# Copy_of_Sheet1.net
KiCad netlist of a schematic drawn in Altium Designer
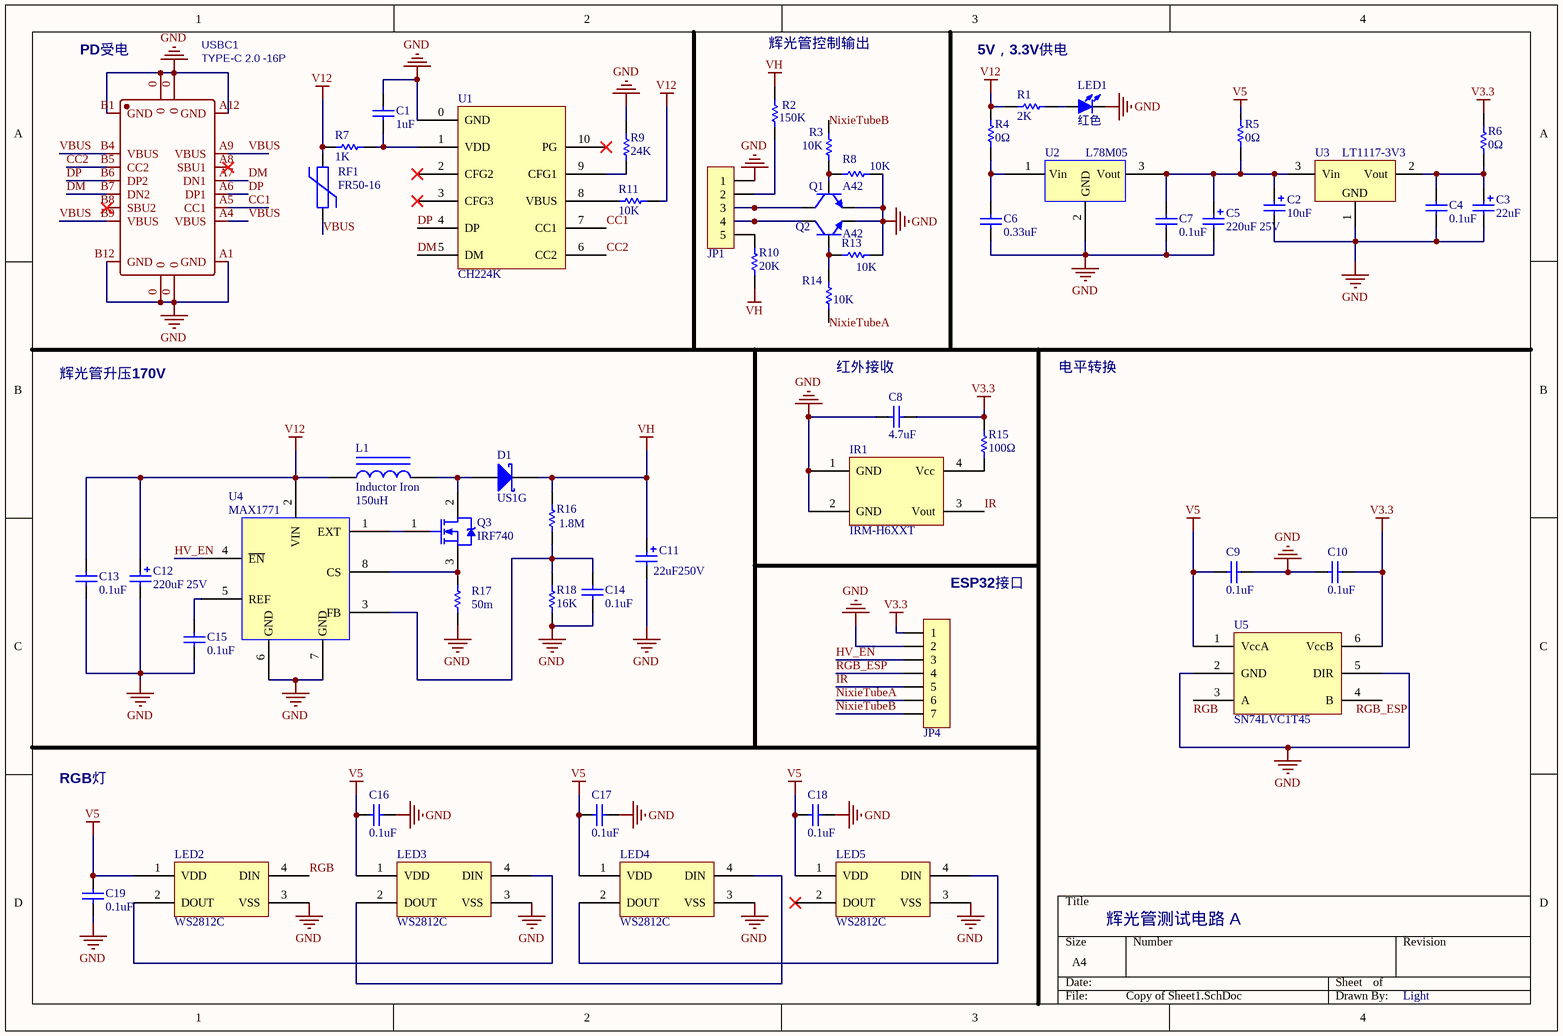
[diagram p0: Copy of Sheet1.SchDoc]

(export (version "E")
  (design (tool "Eeschema 10.0.6"))
  (components
    (comp (ref "C1")
      (value "1uF")
      (footprint "C 0805_L")
      (description "Capacitor")
      (fields (field (name "Comment") "Cap") (field (name "PUBLISHER") "Altium Limited"))
      (libsource (lib "Nixie") (part "Cap"))
    )
    (comp (ref "C2")
      (value "10uF")
      (footprint "CM B(4*5.4)")
      (description "Polarized Capacitor (Radial)")
      (fields (field (name "Comment") "Cap Pol1") (field (name "PUBLISHER") "Altium Limited"))
      (libsource (lib "Nixie") (part "Cap Pol1"))
    )
    (comp (ref "C3")
      (value "22uF")
      (footprint "CD C(6032)")
      (description "Polarized Capacitor (Radial)")
      (fields (field (name "Comment") "Cap Pol1") (field (name "PUBLISHER") "Altium Limited"))
      (libsource (lib "Nixie") (part "Cap Pol1"))
    )
    (comp (ref "C4")
      (value "0.1uF")
      (footprint "C 0805_L")
      (description "Capacitor")
      (fields (field (name "Comment") "Cap") (field (name "PUBLISHER") "Altium Limited"))
      (libsource (lib "Nixie") (part "Cap"))
    )
    (comp (ref "C5")
      (value "220uF 25V")
      (footprint "CM E(8*10.2)")
      (description "Polarized Capacitor (Radial)")
      (fields
        (field (name "VOLTAGE") "16V")
        (field (name "Comment") "Cap Pol1")
        (field (name "PUBLISHER") "Altium Limited")
      )
      (libsource (lib "Nixie") (part "Cap Pol1_2"))
    )
    (comp (ref "C6")
      (value "0.33uF")
      (footprint "C 0805_L")
      (description "Capacitor")
      (fields (field (name "Comment") "Cap") (field (name "PUBLISHER") "Altium Limited"))
      (libsource (lib "Nixie") (part "Cap"))
    )
    (comp (ref "C7")
      (value "0.1uF")
      (footprint "C 0805_L")
      (description "Capacitor")
      (fields (field (name "Comment") "Cap") (field (name "PUBLISHER") "Altium Limited"))
      (libsource (lib "Nixie") (part "Cap"))
    )
    (comp (ref "C8")
      (value "4.7uF")
      (footprint "C 0805_L")
      (description "Capacitor")
      (fields (field (name "Comment") "Cap") (field (name "PUBLISHER") "Altium Limited"))
      (libsource (lib "Nixie") (part "Cap"))
    )
    (comp (ref "C9")
      (value "0.1uF")
      (footprint "C 0805_L")
      (description "Capacitor")
      (fields (field (name "Comment") "Cap") (field (name "PUBLISHER") "Altium Limited"))
      (libsource (lib "Nixie") (part "Cap"))
    )
    (comp (ref "C10")
      (value "0.1uF")
      (footprint "C 0805_L")
      (description "Capacitor")
      (fields (field (name "Comment") "Cap") (field (name "PUBLISHER") "Altium Limited"))
      (libsource (lib "Nixie") (part "Cap"))
    )
    (comp (ref "C11")
      (value "22uF250V")
      (footprint "CAP 5.0*10*16-H - GD")
      (description "Polarized Capacitor (Radial)")
      (fields (field (name "Comment") "Cap Pol1") (field (name "PUBLISHER") "Altium Limited"))
      (libsource (lib "Nixie") (part "Cap Pol1_3"))
    )
    (comp (ref "C12")
      (value "220uF 25V")
      (footprint "CM E(8*10.2)")
      (description "Polarized Capacitor (Radial)")
      (fields
        (field (name "VOLTAGE") "16V")
        (field (name "Comment") "Cap Pol1")
        (field (name "PUBLISHER") "Altium Limited")
      )
      (libsource (lib "Nixie") (part "Cap Pol1_2"))
    )
    (comp (ref "C13")
      (value "0.1uF")
      (footprint "C 0805_L")
      (description "Capacitor")
      (fields (field (name "Comment") "Cap") (field (name "PUBLISHER") "Altium Limited"))
      (libsource (lib "Nixie") (part "Cap"))
    )
    (comp (ref "C14")
      (value "0.1uF")
      (footprint "C 0805_L")
      (description "Capacitor")
      (fields (field (name "Comment") "Cap") (field (name "PUBLISHER") "Altium Limited"))
      (libsource (lib "Nixie") (part "Cap"))
    )
    (comp (ref "C15")
      (value "0.1uF")
      (footprint "C 0805_L")
      (description "Capacitor")
      (fields (field (name "Comment") "Cap") (field (name "PUBLISHER") "Altium Limited"))
      (libsource (lib "Schlib1") (part "Cap"))
    )
    (comp (ref "C16")
      (value "0.1uF")
      (footprint "C 0805_L")
      (description "Capacitor")
      (fields (field (name "Comment") "Cap") (field (name "PUBLISHER") "Altium Limited"))
      (libsource (lib "Nixie") (part "Cap"))
    )
    (comp (ref "C17")
      (value "0.1uF")
      (footprint "C 0805_L")
      (description "Capacitor")
      (fields (field (name "Comment") "Cap") (field (name "PUBLISHER") "Altium Limited"))
      (libsource (lib "Nixie") (part "Cap"))
    )
    (comp (ref "C18")
      (value "0.1uF")
      (footprint "C 0805_L")
      (description "Capacitor")
      (fields (field (name "Comment") "Cap") (field (name "PUBLISHER") "Altium Limited"))
      (libsource (lib "Nixie") (part "Cap"))
    )
    (comp (ref "C19")
      (value "0.1uF")
      (footprint "C 0805_L")
      (description "Capacitor")
      (fields (field (name "Comment") "Cap") (field (name "PUBLISHER") "Altium Limited"))
      (libsource (lib "Nixie") (part "Cap"))
    )
    (comp (ref "D1")
      (value "US1G")
      (footprint "SMA")
      (description "Schottky Diode")
      (fields (field (name "PUBLISHER") "Altium Limited"))
      (libsource (lib "Nixie") (part "D Schottky"))
    )
    (comp (ref "IR1") (value "IRM-H6XXT") (footprint "SMD4_IR") (libsource (lib "Nixie") (part "IR")))
    (comp (ref "JP1")
      (value "HDR-1X5")
      (footprint "XH2.54-LI-5P")
      (description "5P接插件")
      (fields (field (name "版权归属") "封装库来自淘宝 ID：黄晶宝石"))
      (libsource (lib "Nixie") (part "Header 5"))
    )
    (comp (ref "JP4")
      (value "HDR-1X7")
      (footprint "HDR2.54-LI-7P")
      (description "7P接插件")
      (fields (field (name "版权归属") "封装库来自淘宝 ID：黄晶宝石"))
      (libsource (lib "Nixie") (part "Header 7"))
    )
    (comp (ref "L1")
      (value "Inductor Iron")
      (footprint "CDRH127")
      (description "Magnetic-Core Inductor")
      (fields (field (name "ALTIUM_VALUE") "150uH") (field (name "PUBLISHER") "Altium Limited"))
      (libsource (lib "Nixie") (part "Inductor Iron"))
    )
    (comp (ref "LED1")
      (value "红色")
      (footprint "LED 1206R")
      (description "贴片LED")
      (fields (field (name "版权归属") "封装库来自淘宝 ID：黄晶宝石"))
      (libsource (lib "Nixie") (part "LED-SMD"))
    )
    (comp (ref "LED2")
      (value "WS2812C")
      (footprint "WS2812")
      (description "RGB发光管")
      (libsource (lib "Nixie") (part "WS2812"))
    )
    (comp (ref "LED3")
      (value "WS2812C")
      (footprint "WS2812")
      (description "RGB发光管")
      (libsource (lib "Nixie") (part "WS2812"))
    )
    (comp (ref "LED4")
      (value "WS2812C")
      (footprint "WS2812")
      (description "RGB发光管")
      (libsource (lib "Nixie") (part "WS2812"))
    )
    (comp (ref "LED5")
      (value "WS2812C")
      (footprint "WS2812")
      (description "RGB发光管")
      (libsource (lib "Nixie") (part "WS2812"))
    )
    (comp (ref "Q1")
      (value "A42")
      (footprint "SOT23-3L")
      (description "NPN三极管")
      (fields (field (name "PUBLISHER") "Altium Limited"))
      (libsource (lib "Nixie") (part "BCP68"))
    )
    (comp (ref "Q2")
      (value "A42")
      (footprint "SOT23-3L")
      (description "NPN三极管")
      (fields (field (name "PUBLISHER") "Altium Limited"))
      (libsource (lib "Nixie") (part "BCP68"))
    )
    (comp (ref "Q3")
      (value "IRF740")
      (footprint "TO-263-2L")
      (description "N-Channel Power MOSFET")
      (fields (field (name "PUBLISHER") "Altium Limited"))
      (libsource (lib "Nixie") (part "NMOS-2"))
    )
    (comp (ref "R1")
      (value "2K")
      (footprint "R 0805_L")
      (description "Resistor")
      (fields (field (name "PUBLISHER") "Altium Limited"))
      (libsource (lib "Nixie") (part "Resistor"))
    )
    (comp (ref "R2")
      (value "150K")
      (footprint "R 0805_L")
      (description "Semiconductor Resistor")
      (fields (field (name "Comment") "Res Semi") (field (name "PUBLISHER") "Altium Limited"))
      (libsource (lib "Schlib1") (part "Res"))
    )
    (comp (ref "R3")
      (value "10K")
      (footprint "R 0805_L")
      (description "Resistor")
      (fields (field (name "PUBLISHER") "Altium Limited"))
      (libsource (lib "Nixie") (part "Resistor"))
    )
    (comp (ref "R4")
      (value "0Ω")
      (footprint "R 0805_L")
      (description "Resistor")
      (fields (field (name "PUBLISHER") "Altium Limited"))
      (libsource (lib "Nixie") (part "Resistor"))
    )
    (comp (ref "R5")
      (value "0Ω")
      (footprint "R 0805_L")
      (description "Resistor")
      (fields (field (name "PUBLISHER") "Altium Limited"))
      (libsource (lib "Nixie") (part "Resistor"))
    )
    (comp (ref "R6")
      (value "0Ω")
      (footprint "R 0805_L")
      (description "Resistor")
      (fields (field (name "PUBLISHER") "Altium Limited"))
      (libsource (lib "Nixie") (part "Resistor"))
    )
    (comp (ref "R7")
      (value "1K")
      (footprint "R 1206_L")
      (description "Resistor")
      (fields (field (name "PUBLISHER") "Altium Limited"))
      (libsource (lib "Nixie") (part "Resistor"))
    )
    (comp (ref "R8")
      (value "10K")
      (footprint "R 0805_L")
      (description "Resistor")
      (fields (field (name "PUBLISHER") "Altium Limited"))
      (libsource (lib "Nixie") (part "Resistor"))
    )
    (comp (ref "R9")
      (value "24K")
      (footprint "R 0805_L")
      (description "Resistor")
      (fields (field (name "PUBLISHER") "Altium Limited"))
      (libsource (lib "Nixie") (part "Resistor"))
    )
    (comp (ref "R10")
      (value "20K")
      (footprint "R 0805_L")
      (description "Semiconductor Resistor")
      (fields (field (name "Comment") "Res Semi") (field (name "PUBLISHER") "Altium Limited"))
      (libsource (lib "Schlib1") (part "Res"))
    )
    (comp (ref "R11")
      (value "10K")
      (footprint "R 0805_L")
      (description "Resistor")
      (fields (field (name "PUBLISHER") "Altium Limited"))
      (libsource (lib "Nixie") (part "Resistor"))
    )
    (comp (ref "R13")
      (value "10K")
      (footprint "R 0805_L")
      (description "Resistor")
      (fields (field (name "PUBLISHER") "Altium Limited"))
      (libsource (lib "Nixie") (part "Resistor"))
    )
    (comp (ref "R14")
      (value "10K")
      (footprint "R 0805_L")
      (description "Resistor")
      (fields (field (name "PUBLISHER") "Altium Limited"))
      (libsource (lib "Nixie") (part "Resistor"))
    )
    (comp (ref "R15")
      (value "100Ω")
      (footprint "R 0805_L")
      (description "Resistor")
      (fields (field (name "PUBLISHER") "Altium Limited"))
      (libsource (lib "Nixie") (part "Resistor"))
    )
    (comp (ref "R16")
      (value "1.8M")
      (footprint "R 0805_L")
      (description "Semiconductor Resistor")
      (fields (field (name "Comment") "Res Semi") (field (name "PUBLISHER") "Altium Limited"))
      (libsource (lib "Nixie") (part "Res Semi"))
    )
    (comp (ref "R17")
      (value "50m")
      (footprint "R 1206_L")
      (description "Semiconductor Resistor")
      (fields (field (name "Comment") "Res Semi") (field (name "PUBLISHER") "Altium Limited"))
      (libsource (lib "Nixie") (part "Res Semi"))
    )
    (comp (ref "R18")
      (value "16K")
      (footprint "R 0805_L")
      (description "Resistor")
      (fields (field (name "PUBLISHER") "Altium Limited"))
      (libsource (lib "Nixie") (part "Resistor"))
    )
    (comp (ref "RF1")
      (value "FR50-16")
      (footprint "FU 1206")
      (description "PPTC自恢复保险丝")
      (fields (field (name "版权归属") "封装库来自淘宝卖家 ID：黄晶宝石"))
      (libsource (lib "Nixie") (part "PPTC"))
    )
    (comp (ref "U1")
      (value "CH224K")
      (footprint "ESSOP10")
      (description "PD协议受电芯片")
      (libsource (lib "Nixie") (part "CH224K"))
    )
    (comp (ref "U2") (value "L78M05") (footprint "TO-252") (libsource (lib "Nixie") (part "L78M05")))
    (comp (ref "U3")
      (value "LT1117-3V3")
      (footprint "SOT223_L")
      (description "三端稳压芯片")
      (fields (field (name "版权归属") "源创客"))
      (libsource (lib "Nixie") (part "AMS1117"))
    )
    (comp (ref "U4") (value "MAX1771") (footprint "SOIC8") (libsource (lib "Nixie") (part "MAX1771")))
    (comp (ref "U5")
      (value "SN74LVC1T45")
      (footprint "SOT23-6L")
      (description "单路逻辑电平转换")
      (libsource (lib "Nixie") (part "SN74LVC1T45"))
    )
    (comp (ref "USBC1")
      (value "TYPE-C 2.0 -16P")
      (footprint "USB-C-SMD_TYPE-C-USB-5")
      (description "USB2.0 Type-C 母座 16Pin")
      (libsource (lib "Nixie") (part "USB2.0 Type-C 16Pin母座"))
    )
  )
  (nets
    (net (code "1") (name "/CC1") (class "Default")
      (node (ref "U1") (pin "7") (pinfunction "CC1_7") (pintype "passive"))
      (node (ref "USBC1") (pin "A5") (pinfunction "CC1_A5") (pintype "passive"))
    )
    (net (code "2") (name "/CC2") (class "Default")
      (node (ref "U1") (pin "6") (pinfunction "CC2_6") (pintype "passive"))
      (node (ref "USBC1") (pin "B5") (pinfunction "CC2_B5") (pintype "passive"))
    )
    (net (code "3") (name "/DM") (class "Default")
      (node (ref "U1") (pin "5") (pinfunction "DM_5") (pintype "passive"))
      (node (ref "USBC1") (pin "A7") (pinfunction "DN1_A7") (pintype "passive"))
      (node (ref "USBC1") (pin "B7") (pinfunction "DN2_B7") (pintype "passive"))
    )
    (net (code "4") (name "/DP") (class "Default")
      (node (ref "U1") (pin "4") (pinfunction "DP_4") (pintype "passive"))
      (node (ref "USBC1") (pin "A6") (pinfunction "DP1_A6") (pintype "passive"))
      (node (ref "USBC1") (pin "B6") (pinfunction "DP2_B6") (pintype "passive"))
    )
    (net (code "5") (name "/HV_EN") (class "Default")
      (node (ref "JP4") (pin "3") (pinfunction "3_3") (pintype "passive"))
      (node (ref "U4") (pin "4") (pinfunction "~{EN}_4") (pintype "passive"))
    )
    (net (code "6") (name "/IR") (class "Default")
      (node (ref "IR1") (pin "3") (pinfunction "Vout_3") (pintype "passive"))
      (node (ref "JP4") (pin "5") (pinfunction "5_5") (pintype "passive"))
    )
    (net (code "7") (name "/NixieTubeA") (class "Default")
      (node (ref "JP4") (pin "6") (pinfunction "6_6") (pintype "passive"))
      (node (ref "R14") (pin "2") (pinfunction "2_2") (pintype "passive"))
    )
    (net (code "8") (name "/NixieTubeB") (class "Default")
      (node (ref "JP4") (pin "7") (pinfunction "7_7") (pintype "passive"))
      (node (ref "R3") (pin "2") (pinfunction "2_2") (pintype "passive"))
    )
    (net (code "9") (name "/RGB") (class "Default")
      (node (ref "LED2") (pin "4") (pinfunction "DIN_4") (pintype "passive"))
      (node (ref "U5") (pin "3") (pinfunction "A_3") (pintype "passive"))
    )
    (net (code "10") (name "/RGB_ESP") (class "Default")
      (node (ref "JP4") (pin "4") (pinfunction "4_4") (pintype "passive"))
      (node (ref "U5") (pin "4") (pinfunction "B_4") (pintype "passive"))
    )
    (net (code "11") (name "/VBUS") (class "Default")
      (node (ref "RF1") (pin "1") (pinfunction "1_1") (pintype "passive"))
      (node (ref "USBC1") (pin "A4") (pinfunction "VBUS_A4") (pintype "passive"))
      (node (ref "USBC1") (pin "A9") (pinfunction "VBUS_A9") (pintype "passive"))
      (node (ref "USBC1") (pin "B4") (pinfunction "VBUS_B4") (pintype "passive"))
      (node (ref "USBC1") (pin "B9") (pinfunction "VBUS_B9") (pintype "passive"))
    )
    (net (code "12") (name "GND") (class "Default")
      (node (ref "C1") (pin "2") (pinfunction "2_2") (pintype "passive"))
      (node (ref "C10") (pin "2") (pinfunction "2_2") (pintype "passive"))
      (node (ref "C11") (pin "2") (pinfunction "2_2") (pintype "passive"))
      (node (ref "C12") (pin "2") (pinfunction "2_2") (pintype "passive"))
      (node (ref "C13") (pin "1") (pinfunction "1_1") (pintype "passive"))
      (node (ref "C14") (pin "1") (pinfunction "1_1") (pintype "passive"))
      (node (ref "C15") (pin "2") (pinfunction "2_2") (pintype "passive"))
      (node (ref "C16") (pin "1") (pinfunction "1_1") (pintype "passive"))
      (node (ref "C17") (pin "1") (pinfunction "1_1") (pintype "passive"))
      (node (ref "C18") (pin "1") (pinfunction "1_1") (pintype "passive"))
      (node (ref "C19") (pin "1") (pinfunction "1_1") (pintype "passive"))
      (node (ref "C2") (pin "2") (pinfunction "2_2") (pintype "passive"))
      (node (ref "C3") (pin "2") (pinfunction "2_2") (pintype "passive"))
      (node (ref "C4") (pin "1") (pinfunction "1_1") (pintype "passive"))
      (node (ref "C5") (pin "2") (pinfunction "2_2") (pintype "passive"))
      (node (ref "C6") (pin "1") (pinfunction "1_1") (pintype "passive"))
      (node (ref "C7") (pin "1") (pinfunction "1_1") (pintype "passive"))
      (node (ref "C8") (pin "2") (pinfunction "2_2") (pintype "passive"))
      (node (ref "C9") (pin "1") (pinfunction "1_1") (pintype "passive"))
      (node (ref "IR1") (pin "1") (pinfunction "GND_1") (pintype "passive"))
      (node (ref "IR1") (pin "2") (pinfunction "GND_2") (pintype "passive"))
      (node (ref "JP1") (pin "1") (pinfunction "1_1") (pintype "passive"))
      (node (ref "JP4") (pin "2") (pinfunction "2_2") (pintype "passive"))
      (node (ref "LED1") (pin "2") (pinfunction "K_2") (pintype "passive"))
      (node (ref "LED2") (pin "3") (pinfunction "VSS_3") (pintype "passive"))
      (node (ref "LED3") (pin "3") (pinfunction "VSS_3") (pintype "passive"))
      (node (ref "LED4") (pin "3") (pinfunction "VSS_3") (pintype "passive"))
      (node (ref "LED5") (pin "3") (pinfunction "VSS_3") (pintype "passive"))
      (node (ref "Q1") (pin "2") (pinfunction "E_2") (pintype "passive"))
      (node (ref "Q2") (pin "2") (pinfunction "E_2") (pintype "passive"))
      (node (ref "R13") (pin "2") (pinfunction "2_2") (pintype "passive"))
      (node (ref "R17") (pin "2") (pinfunction "2_2") (pintype "passive"))
      (node (ref "R18") (pin "1") (pinfunction "1_1") (pintype "passive"))
      (node (ref "R8") (pin "2") (pinfunction "2_2") (pintype "passive"))
      (node (ref "R9") (pin "1") (pinfunction "1_1") (pintype "passive"))
      (node (ref "U1") (pin "0") (pinfunction "GND_0") (pintype "passive"))
      (node (ref "U2") (pin "2") (pinfunction "GND_2") (pintype "passive"))
      (node (ref "U3") (pin "1") (pinfunction "GND_1") (pintype "passive"))
      (node (ref "U4") (pin "6") (pinfunction "GND_6") (pintype "passive"))
      (node (ref "U4") (pin "7") (pinfunction "GND_7") (pintype "passive"))
      (node (ref "U5") (pin "2") (pinfunction "GND_2") (pintype "passive"))
      (node (ref "U5") (pin "5") (pinfunction "DIR_5") (pintype "passive"))
      (node (ref "USBC1") (pin "0") (pinfunction "0_0") (pintype "passive"))
      (node (ref "USBC1") (pin "A1") (pinfunction "GND_A1") (pintype "passive"))
      (node (ref "USBC1") (pin "A12") (pinfunction "GND_A12") (pintype "passive"))
      (node (ref "USBC1") (pin "B1") (pinfunction "GND_B1") (pintype "passive"))
      (node (ref "USBC1") (pin "B12") (pinfunction "GND_B12") (pintype "passive"))
    )
    (net (code "13") (name "Net-(D1-A)") (class "Default")
      (node (ref "D1") (pin "1") (pinfunction "A_1") (pintype "passive"))
      (node (ref "L1") (pin "2") (pinfunction "2_2") (pintype "passive"))
      (node (ref "Q3") (pin "2") (pinfunction "D_2") (pintype "passive"))
    )
    (net (code "14") (name "Net-(IR1-Vcc)") (class "Default")
      (node (ref "IR1") (pin "4") (pinfunction "Vcc_4") (pintype "passive"))
      (node (ref "R15") (pin "1") (pinfunction "1_1") (pintype "passive"))
    )
    (net (code "15") (name "Net-(JP1-Pad2)") (class "Default")
      (node (ref "JP1") (pin "2") (pinfunction "2_2") (pintype "passive"))
      (node (ref "R2") (pin "1") (pinfunction "1_1") (pintype "passive"))
    )
    (net (code "16") (name "Net-(JP1-Pad5)") (class "Default")
      (node (ref "JP1") (pin "5") (pinfunction "5_5") (pintype "passive"))
      (node (ref "R10") (pin "2") (pinfunction "2_2") (pintype "passive"))
    )
    (net (code "17") (name "Net-(LED1-A)") (class "Default")
      (node (ref "LED1") (pin "1") (pinfunction "A_1") (pintype "passive"))
      (node (ref "R1") (pin "1") (pinfunction "1_1") (pintype "passive"))
    )
    (net (code "18") (name "Net-(LED2-DOUT)") (class "Default")
      (node (ref "LED2") (pin "2") (pinfunction "DOUT_2") (pintype "passive"))
      (node (ref "LED3") (pin "4") (pinfunction "DIN_4") (pintype "passive"))
    )
    (net (code "19") (name "Net-(LED3-DOUT)") (class "Default")
      (node (ref "LED3") (pin "2") (pinfunction "DOUT_2") (pintype "passive"))
      (node (ref "LED4") (pin "4") (pinfunction "DIN_4") (pintype "passive"))
    )
    (net (code "20") (name "Net-(LED4-DOUT)") (class "Default")
      (node (ref "LED4") (pin "2") (pinfunction "DOUT_2") (pintype "passive"))
      (node (ref "LED5") (pin "4") (pinfunction "DIN_4") (pintype "passive"))
    )
    (net (code "21") (name "Net-(Q1-B)") (class "Default")
      (node (ref "Q1") (pin "1") (pinfunction "B_1") (pintype "passive"))
      (node (ref "R3") (pin "1") (pinfunction "1_1") (pintype "passive"))
      (node (ref "R8") (pin "1") (pinfunction "1_1") (pintype "passive"))
    )
    (net (code "22") (name "Net-(Q1-C)") (class "Default")
      (node (ref "JP1") (pin "3") (pinfunction "3_3") (pintype "passive"))
      (node (ref "Q1") (pin "3") (pinfunction "C_3") (pintype "passive"))
    )
    (net (code "23") (name "Net-(Q2-B)") (class "Default")
      (node (ref "Q2") (pin "1") (pinfunction "B_1") (pintype "passive"))
      (node (ref "R13") (pin "1") (pinfunction "1_1") (pintype "passive"))
      (node (ref "R14") (pin "1") (pinfunction "1_1") (pintype "passive"))
    )
    (net (code "24") (name "Net-(Q2-C)") (class "Default")
      (node (ref "JP1") (pin "4") (pinfunction "4_4") (pintype "passive"))
      (node (ref "Q2") (pin "3") (pinfunction "C_3") (pintype "passive"))
    )
    (net (code "25") (name "Net-(Q3-G)") (class "Default")
      (node (ref "Q3") (pin "1") (pinfunction "G_1") (pintype "passive"))
      (node (ref "U4") (pin "1") (pinfunction "EXT_1") (pintype "passive"))
    )
    (net (code "26") (name "Net-(Q3-S)") (class "Default")
      (node (ref "Q3") (pin "3") (pinfunction "S_3") (pintype "passive"))
      (node (ref "R17") (pin "1") (pinfunction "1_1") (pintype "passive"))
      (node (ref "U4") (pin "8") (pinfunction "CS_8") (pintype "passive"))
    )
    (net (code "27") (name "Net-(U1-CFG1)") (class "Default")
      (node (ref "R9") (pin "2") (pinfunction "2_2") (pintype "passive"))
      (node (ref "U1") (pin "9") (pinfunction "CFG1_9") (pintype "passive"))
    )
    (net (code "28") (name "Net-(U1-VBUS)") (class "Default")
      (node (ref "R11") (pin "2") (pinfunction "2_2") (pintype "passive"))
      (node (ref "U1") (pin "8") (pinfunction "VBUS_8") (pintype "passive"))
    )
    (net (code "29") (name "Net-(U1-VDD)") (class "Default")
      (node (ref "C1") (pin "1") (pinfunction "1_1") (pintype "passive"))
      (node (ref "R7") (pin "1") (pinfunction "1_1") (pintype "passive"))
      (node (ref "U1") (pin "1") (pinfunction "VDD_1") (pintype "passive"))
    )
    (net (code "30") (name "Net-(U2-Vin)") (class "Default")
      (node (ref "C6") (pin "2") (pinfunction "2_2") (pintype "passive"))
      (node (ref "R4") (pin "1") (pinfunction "1_1") (pintype "passive"))
      (node (ref "U2") (pin "1") (pinfunction "Vin_1") (pintype "passive"))
    )
    (net (code "31") (name "Net-(U2-Vout)") (class "Default")
      (node (ref "C2") (pin "1") (pinfunction "1_1") (pintype "passive"))
      (node (ref "C5") (pin "1") (pinfunction "1_1") (pintype "passive"))
      (node (ref "C7") (pin "2") (pinfunction "2_2") (pintype "passive"))
      (node (ref "R5") (pin "1") (pinfunction "1_1") (pintype "passive"))
      (node (ref "U2") (pin "3") (pinfunction "Vout_3") (pintype "passive"))
      (node (ref "U3") (pin "3") (pinfunction "Vin_3") (pintype "passive"))
    )
    (net (code "32") (name "Net-(U3-Vout)") (class "Default")
      (node (ref "C3") (pin "1") (pinfunction "1_1") (pintype "passive"))
      (node (ref "C4") (pin "2") (pinfunction "2_2") (pintype "passive"))
      (node (ref "R6") (pin "1") (pinfunction "1_1") (pintype "passive"))
      (node (ref "U3") (pin "2") (pinfunction "Vout_2") (pintype "passive"))
    )
    (net (code "33") (name "Net-(U4-FB)") (class "Default")
      (node (ref "C14") (pin "2") (pinfunction "2_2") (pintype "passive"))
      (node (ref "R16") (pin "2") (pinfunction "2_2") (pintype "passive"))
      (node (ref "R18") (pin "2") (pinfunction "2_2") (pintype "passive"))
      (node (ref "U4") (pin "3") (pinfunction "FB_3") (pintype "passive"))
    )
    (net (code "34") (name "Net-(U4-REF)") (class "Default")
      (node (ref "C15") (pin "1") (pinfunction "1_1") (pintype "passive"))
      (node (ref "U4") (pin "5") (pinfunction "REF_5") (pintype "passive"))
    )
    (net (code "35") (name "V3.3") (class "Default")
      (node (ref "C10") (pin "1") (pinfunction "1_1") (pintype "passive"))
      (node (ref "C8") (pin "1") (pinfunction "1_1") (pintype "passive"))
      (node (ref "JP4") (pin "1") (pinfunction "1_1") (pintype "passive"))
      (node (ref "R15") (pin "2") (pinfunction "2_2") (pintype "passive"))
      (node (ref "R6") (pin "2") (pinfunction "2_2") (pintype "passive"))
      (node (ref "U5") (pin "6") (pinfunction "VccB_6") (pintype "passive"))
    )
    (net (code "36") (name "V5") (class "Default")
      (node (ref "C16") (pin "2") (pinfunction "2_2") (pintype "passive"))
      (node (ref "C17") (pin "2") (pinfunction "2_2") (pintype "passive"))
      (node (ref "C18") (pin "2") (pinfunction "2_2") (pintype "passive"))
      (node (ref "C19") (pin "2") (pinfunction "2_2") (pintype "passive"))
      (node (ref "C9") (pin "2") (pinfunction "2_2") (pintype "passive"))
      (node (ref "LED2") (pin "1") (pinfunction "VDD_1") (pintype "passive"))
      (node (ref "LED3") (pin "1") (pinfunction "VDD_1") (pintype "passive"))
      (node (ref "LED4") (pin "1") (pinfunction "VDD_1") (pintype "passive"))
      (node (ref "LED5") (pin "1") (pinfunction "VDD_1") (pintype "passive"))
      (node (ref "R5") (pin "2") (pinfunction "2_2") (pintype "passive"))
      (node (ref "U5") (pin "1") (pinfunction "VccA_1") (pintype "passive"))
    )
    (net (code "37") (name "V12") (class "Default")
      (node (ref "C12") (pin "1") (pinfunction "1_1") (pintype "passive"))
      (node (ref "C13") (pin "2") (pinfunction "2_2") (pintype "passive"))
      (node (ref "L1") (pin "1") (pinfunction "1_1") (pintype "passive"))
      (node (ref "R1") (pin "2") (pinfunction "2_2") (pintype "passive"))
      (node (ref "R11") (pin "1") (pinfunction "1_1") (pintype "passive"))
      (node (ref "R4") (pin "2") (pinfunction "2_2") (pintype "passive"))
      (node (ref "R7") (pin "2") (pinfunction "2_2") (pintype "passive"))
      (node (ref "RF1") (pin "2") (pinfunction "2_2") (pintype "passive"))
      (node (ref "U4") (pin "2") (pinfunction "VIN_2") (pintype "passive"))
    )
    (net (code "38") (name "VH") (class "Default")
      (node (ref "C11") (pin "1") (pinfunction "1_1") (pintype "passive"))
      (node (ref "D1") (pin "2") (pinfunction "K_2") (pintype "passive"))
      (node (ref "R10") (pin "1") (pinfunction "1_1") (pintype "passive"))
      (node (ref "R16") (pin "1") (pinfunction "1_1") (pintype "passive"))
      (node (ref "R2") (pin "2") (pinfunction "2_2") (pintype "passive"))
    )
    (net (code "39") (name "unconnected-(LED5-DOUT-Pad2)") (class "Default")
      (node (ref "LED5") (pin "2") (pinfunction "DOUT_2") (pintype "passive+no_connect"))
    )
    (net (code "40") (name "unconnected-(U1-CFG2-Pad2)") (class "Default")
      (node (ref "U1") (pin "2") (pinfunction "CFG2_2") (pintype "passive+no_connect"))
    )
    (net (code "41") (name "unconnected-(U1-CFG3-Pad3)") (class "Default")
      (node (ref "U1") (pin "3") (pinfunction "CFG3_3") (pintype "passive+no_connect"))
    )
    (net (code "42") (name "unconnected-(U1-PG-Pad10)") (class "Default")
      (node (ref "U1") (pin "10") (pinfunction "PG_10") (pintype "passive+no_connect"))
    )
    (net (code "43") (name "unconnected-(USBC1-SBU1-PadA8)") (class "Default")
      (node (ref "USBC1") (pin "A8") (pinfunction "SBU1_A8") (pintype "passive+no_connect"))
    )
    (net (code "44") (name "unconnected-(USBC1-SBU2-PadB8)") (class "Default")
      (node (ref "USBC1") (pin "B8") (pinfunction "SBU2_B8") (pintype "passive+no_connect"))
    )
  )
)
